# d_main2.net
KiCad netlist of a schematic drawn in EAGLE
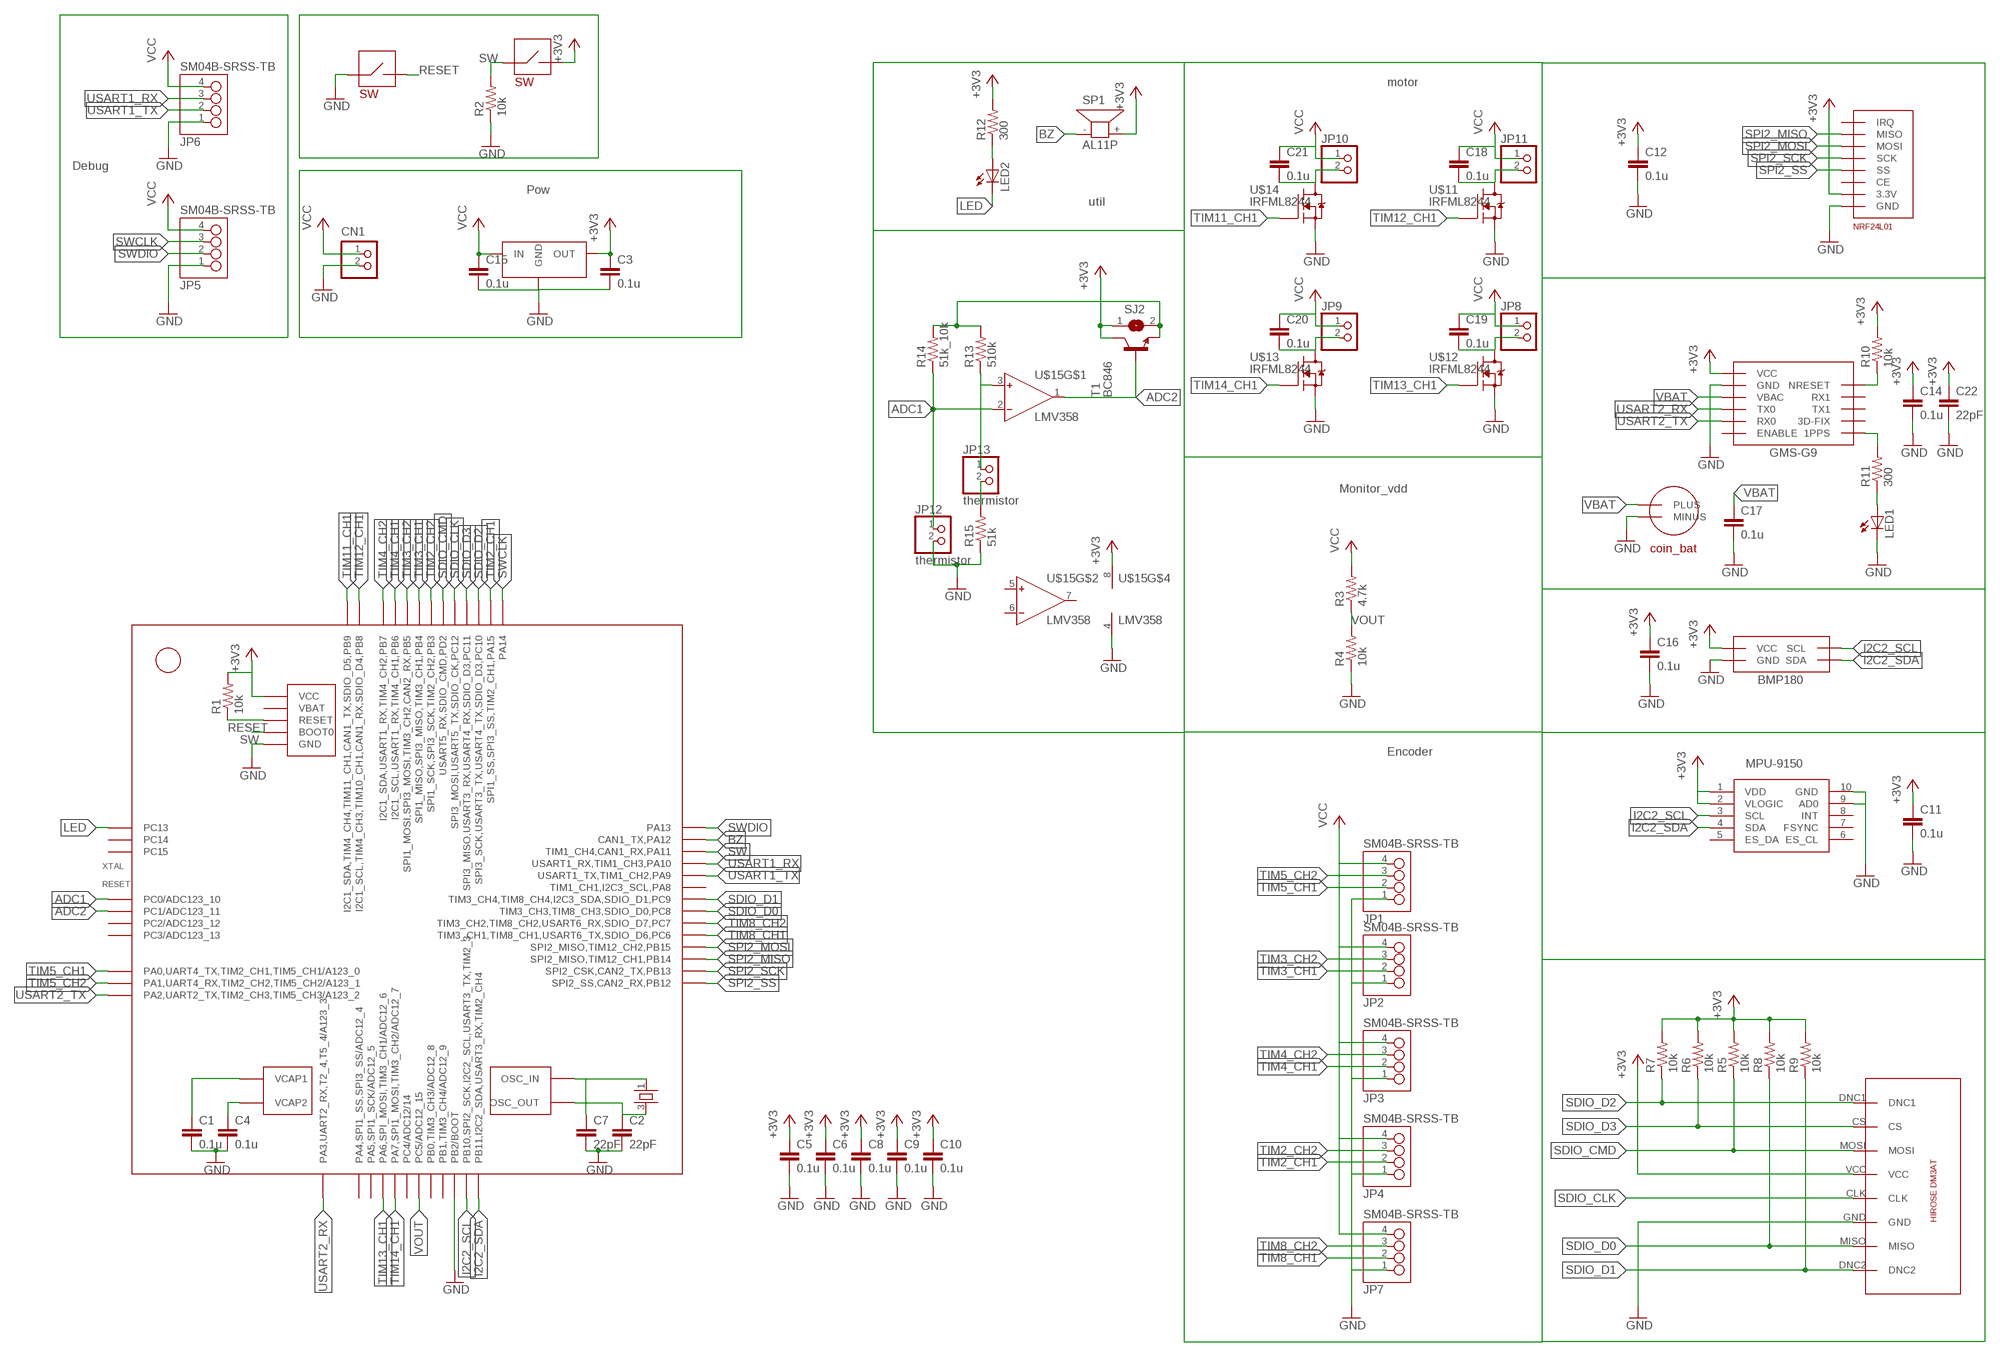
[diagram p0: schematic, sheet 1, part 1 of 2]
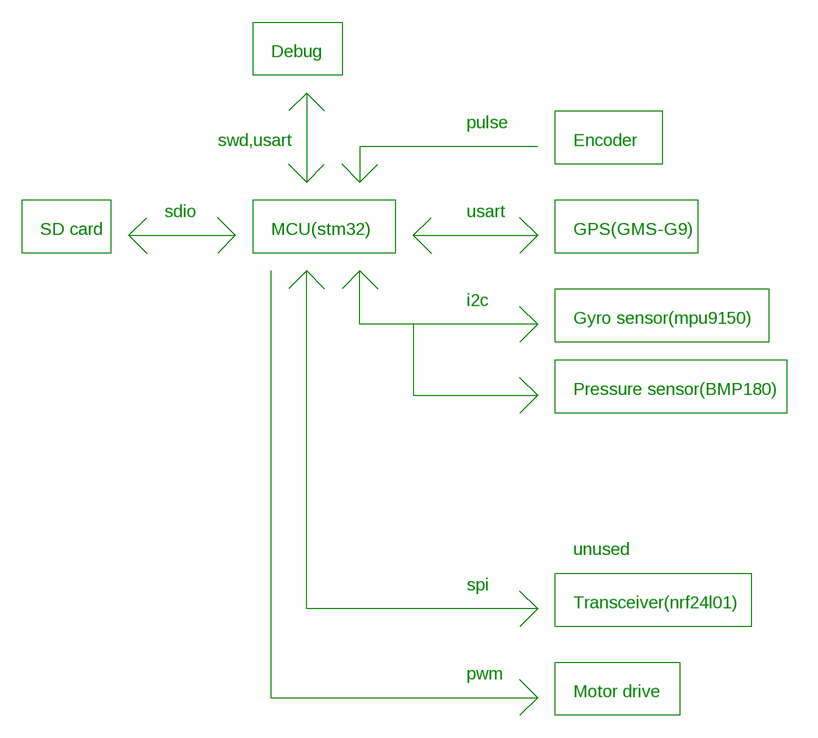
[diagram p1: schematic, sheet 1, part 2 of 2]

(export (version "E")
  (design (tool "Eeschema 10.0.6"))
  (components
    (comp (ref "C1")
      (value "0.1u")
      (footprint "eagle-import:C0603K")
      (libsource (lib "eagle-import") (part "C-EUC0603K"))
    )
    (comp (ref "C2")
      (value "22pF")
      (footprint "eagle-import:C0603K")
      (libsource (lib "eagle-import") (part "C-EUC0603K"))
    )
    (comp (ref "C3")
      (value "0.1u")
      (footprint "eagle-import:C0603K")
      (libsource (lib "eagle-import") (part "C-EUC0603K"))
    )
    (comp (ref "C4")
      (value "0.1u")
      (footprint "eagle-import:C0603K")
      (libsource (lib "eagle-import") (part "C-EUC0603K"))
    )
    (comp (ref "C5")
      (value "0.1u")
      (footprint "eagle-import:C0603K")
      (libsource (lib "eagle-import") (part "C-EUC0603K"))
    )
    (comp (ref "C6")
      (value "0.1u")
      (footprint "eagle-import:C0603K")
      (libsource (lib "eagle-import") (part "C-EUC0603K"))
    )
    (comp (ref "C7")
      (value "22pF")
      (footprint "eagle-import:C0603K")
      (libsource (lib "eagle-import") (part "C-EUC0603K"))
    )
    (comp (ref "C8")
      (value "0.1u")
      (footprint "eagle-import:C0603K")
      (libsource (lib "eagle-import") (part "C-EUC0603K"))
    )
    (comp (ref "C9")
      (value "0.1u")
      (footprint "eagle-import:C0603K")
      (libsource (lib "eagle-import") (part "C-EUC0603K"))
    )
    (comp (ref "C10")
      (value "0.1u")
      (footprint "eagle-import:C0603K")
      (libsource (lib "eagle-import") (part "C-EUC0603K"))
    )
    (comp (ref "C11")
      (value "0.1u")
      (footprint "eagle-import:C0603K")
      (libsource (lib "eagle-import") (part "C-EUC0603K"))
    )
    (comp (ref "C12")
      (value "0.1u")
      (footprint "eagle-import:C0603K")
      (libsource (lib "eagle-import") (part "C-EUC0603K"))
    )
    (comp (ref "C14")
      (value "0.1u")
      (footprint "eagle-import:C0603K")
      (libsource (lib "eagle-import") (part "C-EUC0603K"))
    )
    (comp (ref "C15")
      (value "0.1u")
      (footprint "eagle-import:C0603K")
      (libsource (lib "eagle-import") (part "C-EUC0603K"))
    )
    (comp (ref "C16")
      (value "0.1u")
      (footprint "eagle-import:C0603K")
      (libsource (lib "eagle-import") (part "C-EUC0603K"))
    )
    (comp (ref "C17")
      (value "0.1u")
      (footprint "eagle-import:C0603K")
      (libsource (lib "eagle-import") (part "C-EUC0603K"))
    )
    (comp (ref "C18")
      (value "0.1u")
      (footprint "eagle-import:C0603K")
      (libsource (lib "eagle-import") (part "C-EUC0603K"))
    )
    (comp (ref "C19")
      (value "0.1u")
      (footprint "eagle-import:C0603K")
      (libsource (lib "eagle-import") (part "C-EUC0603K"))
    )
    (comp (ref "C20")
      (value "0.1u")
      (footprint "eagle-import:C0603K")
      (libsource (lib "eagle-import") (part "C-EUC0603K"))
    )
    (comp (ref "C21")
      (value "0.1u")
      (footprint "eagle-import:C0603K")
      (libsource (lib "eagle-import") (part "C-EUC0603K"))
    )
    (comp (ref "C22")
      (value "22pF")
      (footprint "eagle-import:C0603K")
      (libsource (lib "eagle-import") (part "C-EUC0603K"))
    )
    (comp (ref "CN1")
      (value "S2B-XASK-1")
      (footprint "eagle-import:S2B-XASK-1")
      (libsource (lib "eagle-import") (part "S2B-XASK-1"))
    )
    (comp (ref "JP1")
      (value "SM04B-SRSS-TB")
      (footprint "eagle-import:SM04B-SRSS-TB")
      (libsource (lib "eagle-import") (part "SM04B-SRSS-TB"))
    )
    (comp (ref "JP2")
      (value "SM04B-SRSS-TB")
      (footprint "eagle-import:SM04B-SRSS-TB")
      (libsource (lib "eagle-import") (part "SM04B-SRSS-TB"))
    )
    (comp (ref "JP3")
      (value "SM04B-SRSS-TB")
      (footprint "eagle-import:SM04B-SRSS-TB")
      (libsource (lib "eagle-import") (part "SM04B-SRSS-TB"))
    )
    (comp (ref "JP4")
      (value "SM04B-SRSS-TB")
      (footprint "eagle-import:SM04B-SRSS-TB")
      (libsource (lib "eagle-import") (part "SM04B-SRSS-TB"))
    )
    (comp (ref "JP5")
      (value "SM04B-SRSS-TB")
      (footprint "eagle-import:SM04B-SRSS-TB")
      (libsource (lib "eagle-import") (part "SM04B-SRSS-TB"))
    )
    (comp (ref "JP6")
      (value "SM04B-SRSS-TB")
      (footprint "eagle-import:SM04B-SRSS-TB")
      (libsource (lib "eagle-import") (part "SM04B-SRSS-TB"))
    )
    (comp (ref "JP7")
      (value "SM04B-SRSS-TB")
      (footprint "eagle-import:SM04B-SRSS-TB")
      (libsource (lib "eagle-import") (part "SM04B-SRSS-TB"))
    )
    (comp (ref "JP8")
      (value "PINHD-1X2")
      (footprint "eagle-import:1X02")
      (libsource (lib "eagle-import") (part "PINHD-1X2"))
    )
    (comp (ref "JP9")
      (value "PINHD-1X2")
      (footprint "eagle-import:1X02")
      (libsource (lib "eagle-import") (part "PINHD-1X2"))
    )
    (comp (ref "JP10")
      (value "PINHD-1X2")
      (footprint "eagle-import:1X02")
      (libsource (lib "eagle-import") (part "PINHD-1X2"))
    )
    (comp (ref "JP11")
      (value "PINHD-1X2")
      (footprint "eagle-import:1X02")
      (libsource (lib "eagle-import") (part "PINHD-1X2"))
    )
    (comp (ref "JP12")
      (value "thermistor")
      (footprint "eagle-import:1X02")
      (libsource (lib "eagle-import") (part "PINHD-1X2"))
    )
    (comp (ref "JP13")
      (value "thermistor")
      (footprint "eagle-import:1X02")
      (libsource (lib "eagle-import") (part "PINHD-1X2"))
    )
    (comp (ref "LED1")
      (value "LEDCHIP-LED0603")
      (footprint "eagle-import:CHIP-LED0603")
      (libsource (lib "eagle-import") (part "LEDCHIP-LED0603"))
    )
    (comp (ref "LED2")
      (value "LEDCHIP-LED0603")
      (footprint "eagle-import:CHIP-LED0603")
      (libsource (lib "eagle-import") (part "LEDCHIP-LED0603"))
    )
    (comp (ref "R1")
      (value "10k")
      (footprint "eagle-import:R0603")
      (libsource (lib "eagle-import") (part "R-US_R0603"))
    )
    (comp (ref "R2")
      (value "10k")
      (footprint "eagle-import:R0603")
      (libsource (lib "eagle-import") (part "R-US_R0603"))
    )
    (comp (ref "R3")
      (value "4.7k")
      (footprint "eagle-import:R0603")
      (libsource (lib "eagle-import") (part "R-US_R0603"))
    )
    (comp (ref "R4")
      (value "10k")
      (footprint "eagle-import:R0603")
      (libsource (lib "eagle-import") (part "R-US_R0603"))
    )
    (comp (ref "R5")
      (value "10k")
      (footprint "eagle-import:R0603")
      (libsource (lib "eagle-import") (part "R-US_R0603"))
    )
    (comp (ref "R6")
      (value "10k")
      (footprint "eagle-import:R0603")
      (libsource (lib "eagle-import") (part "R-US_R0603"))
    )
    (comp (ref "R7")
      (value "10k")
      (footprint "eagle-import:R0603")
      (libsource (lib "eagle-import") (part "R-US_R0603"))
    )
    (comp (ref "R8")
      (value "10k")
      (footprint "eagle-import:R0603")
      (libsource (lib "eagle-import") (part "R-US_R0603"))
    )
    (comp (ref "R9")
      (value "10k")
      (footprint "eagle-import:R0603")
      (libsource (lib "eagle-import") (part "R-US_R0603"))
    )
    (comp (ref "R10")
      (value "10k")
      (footprint "eagle-import:R0603")
      (libsource (lib "eagle-import") (part "R-US_R0603"))
    )
    (comp (ref "R11")
      (value "300")
      (footprint "eagle-import:R0603")
      (libsource (lib "eagle-import") (part "R-US_R0603"))
    )
    (comp (ref "R12")
      (value "300")
      (footprint "eagle-import:R0603")
      (libsource (lib "eagle-import") (part "R-US_R0603"))
    )
    (comp (ref "R13")
      (value "510k")
      (footprint "eagle-import:R0603")
      (libsource (lib "eagle-import") (part "R-US_R0603"))
    )
    (comp (ref "R14")
      (value "51k_10k")
      (footprint "eagle-import:R0603")
      (libsource (lib "eagle-import") (part "R-US_R0603"))
    )
    (comp (ref "R15")
      (value "51k")
      (footprint "eagle-import:R0603")
      (libsource (lib "eagle-import") (part "R-US_R0603"))
    )
    (comp (ref "SJ2") (value "SJ") (footprint "eagle-import:SJ") (libsource (lib "eagle-import") (part "SJ")))
    (comp (ref "SP1")
      (value "AL11P")
      (footprint "eagle-import:AL11P")
      (libsource (lib "eagle-import") (part "AL11P"))
    )
    (comp (ref "STM32F405RGT6")
      (value "STM32F405_T")
      (footprint "eagle-import:LQFP64")
      (libsource (lib "eagle-import") (part "STM32F405_T"))
    )
    (comp (ref "T1")
      (value "BC846")
      (footprint "eagle-import:SOT23")
      (libsource (lib "eagle-import") (part "BC846"))
    )
    (comp (ref "U$1")
      (value "GMS-G9")
      (footprint "eagle-import:GMS-G9")
      (libsource (lib "eagle-import") (part "GMS-G9"))
    )
    (comp (ref "U$2")
      (value "BMP180")
      (footprint "eagle-import:BMP180")
      (libsource (lib "eagle-import") (part "BMP180"))
    )
    (comp (ref "U$3")
      (value "NRF24L01")
      (footprint "eagle-import:NRF24L01")
      (libsource (lib "eagle-import") (part "NRF24L01"))
    )
    (comp (ref "U$4")
      (value "1056TR")
      (footprint "eagle-import:1056TR")
      (libsource (lib "eagle-import") (part "1056TR"))
    )
    (comp (ref "U$5")
      (value "DM3AT")
      (footprint "eagle-import:DM3AT")
      (libsource (lib "eagle-import") (part "DM3AT"))
    )
    (comp (ref "U$6")
      (value "SWTVBP06-B043CB-B")
      (footprint "eagle-import:SW")
      (libsource (lib "eagle-import") (part "SWTVBP06-B043CB-B"))
    )
    (comp (ref "U$7")
      (value "SWTVBP06-B043CB-B")
      (footprint "eagle-import:SW")
      (libsource (lib "eagle-import") (part "SWTVBP06-B043CB-B"))
    )
    (comp (ref "U$8")
      (value "AP7361-33E")
      (footprint "eagle-import:SOT223")
      (libsource (lib "eagle-import") (part "AP7361-33E"))
    )
    (comp (ref "U$9")
      (value "25MHz")
      (footprint "eagle-import:ASF")
      (libsource (lib "eagle-import") (part "ASF_T"))
    )
    (comp (ref "U$10")
      (value "MPU-9150")
      (footprint "eagle-import:MPU-9150")
      (libsource (lib "eagle-import") (part "MPU-9150"))
    )
    (comp (ref "U$11")
      (value "IRFML8244")
      (footprint "eagle-import:SOT23")
      (libsource (lib "eagle-import") (part "IRFML8244"))
    )
    (comp (ref "U$12")
      (value "IRFML8244")
      (footprint "eagle-import:SOT23")
      (libsource (lib "eagle-import") (part "IRFML8244"))
    )
    (comp (ref "U$13")
      (value "IRFML8244")
      (footprint "eagle-import:SOT23")
      (libsource (lib "eagle-import") (part "IRFML8244"))
    )
    (comp (ref "U$14")
      (value "IRFML8244")
      (footprint "eagle-import:SOT23")
      (libsource (lib "eagle-import") (part "IRFML8244"))
    )
    (comp (ref "U$15")
      (value "LMV358")
      (footprint "eagle-import:SO8")
      (libsource (lib "eagle-import") (part "LMV358"))
    )
  )
  (nets
    (net (code "1") (name "+3V3") (class "Default")
      (node (ref "C10") (pin "1") (pinfunction "1_1") (pintype "passive"))
      (node (ref "C11") (pin "1") (pinfunction "1_1") (pintype "passive"))
      (node (ref "C12") (pin "1") (pinfunction "1_1") (pintype "passive"))
      (node (ref "C14") (pin "1") (pinfunction "1_1") (pintype "passive"))
      (node (ref "C16") (pin "1") (pinfunction "1_1") (pintype "passive"))
      (node (ref "C22") (pin "1") (pinfunction "1_1") (pintype "passive"))
      (node (ref "C3") (pin "1") (pinfunction "1_1") (pintype "passive"))
      (node (ref "C5") (pin "1") (pinfunction "1_1") (pintype "passive"))
      (node (ref "C6") (pin "1") (pinfunction "1_1") (pintype "passive"))
      (node (ref "C8") (pin "1") (pinfunction "1_1") (pintype "passive"))
      (node (ref "C9") (pin "1") (pinfunction "1_1") (pintype "passive"))
      (node (ref "R1") (pin "2") (pinfunction "2_2") (pintype "passive"))
      (node (ref "R10") (pin "2") (pinfunction "2_2") (pintype "passive"))
      (node (ref "R12") (pin "2") (pinfunction "2_2") (pintype "passive"))
      (node (ref "R5") (pin "2") (pinfunction "2_2") (pintype "passive"))
      (node (ref "R6") (pin "2") (pinfunction "2_2") (pintype "passive"))
      (node (ref "R7") (pin "2") (pinfunction "2_2") (pintype "passive"))
      (node (ref "R8") (pin "2") (pinfunction "2_2") (pintype "passive"))
      (node (ref "R9") (pin "2") (pinfunction "2_2") (pintype "passive"))
      (node (ref "SJ2") (pin "1") (pinfunction "1_1") (pintype "passive"))
      (node (ref "SP1") (pin "+") (pinfunction "2_+") (pintype "passive"))
      (node (ref "STM32F405RGT6") (pin "13") (pinfunction "VCC_13") (pintype "bidirectional"))
      (node (ref "STM32F405RGT6") (pin "19") (pinfunction "VCC_19") (pintype "bidirectional"))
      (node (ref "STM32F405RGT6") (pin "32") (pinfunction "VCC_32") (pintype "bidirectional"))
      (node (ref "STM32F405RGT6") (pin "48") (pinfunction "VCC_48") (pintype "bidirectional"))
      (node (ref "STM32F405RGT6") (pin "64") (pinfunction "VCC_64") (pintype "bidirectional"))
      (node (ref "T1") (pin "3") (pinfunction "C_3") (pintype "passive"))
      (node (ref "U$1") (pin "VCC") (pinfunction "VCC_VCC") (pintype "bidirectional"))
      (node (ref "U$10") (pin "1") (pinfunction "VDD_1") (pintype "bidirectional"))
      (node (ref "U$10") (pin "2") (pinfunction "VLOGIC_2") (pintype "bidirectional"))
      (node (ref "U$15") (pin "8") (pinfunction "V+_8") (pintype "power_in"))
      (node (ref "U$2") (pin "VDD") (pinfunction "VCC_VDD") (pintype "bidirectional"))
      (node (ref "U$2") (pin "VDDIO") (pinfunction "VCC_VDDIO") (pintype "bidirectional"))
      (node (ref "U$3") (pin "3.3V") (pinfunction "3.3V_3.3V") (pintype "bidirectional"))
      (node (ref "U$5") (pin "VCC") (pinfunction "VCC_VCC") (pintype "bidirectional"))
      (node (ref "U$7") (pin "P$2") (pinfunction "P$2_P$2") (pintype "bidirectional"))
      (node (ref "U$8") (pin "OUT") (pinfunction "OUT_OUT") (pintype "bidirectional"))
    )
    (net (code "2") (name "/RESET") (class "Default")
      (node (ref "R1") (pin "1") (pinfunction "1_1") (pintype "passive"))
      (node (ref "STM32F405RGT6") (pin "7") (pinfunction "RESET_7") (pintype "bidirectional"))
      (node (ref "U$6") (pin "P$2") (pinfunction "P$2_P$2") (pintype "bidirectional"))
    )
    (net (code "3") (name "ADC1") (class "Default")
      (node (ref "JP12") (pin "1") (pinfunction "1_1") (pintype "passive"))
      (node (ref "R14") (pin "1") (pinfunction "1_1") (pintype "passive"))
      (node (ref "STM32F405RGT6") (pin "8") (pinfunction "PC0/ADC123_10_8") (pintype "bidirectional"))
      (node (ref "U$15") (pin "2") (pinfunction "IN-_2") (pintype "input"))
    )
    (net (code "4") (name "ADC2") (class "Default")
      (node (ref "STM32F405RGT6") (pin "9") (pinfunction "PC1/ADC123_11_9") (pintype "bidirectional"))
      (node (ref "T1") (pin "1") (pinfunction "B_1") (pintype "passive"))
      (node (ref "U$15") (pin "1") (pinfunction "OUT_1") (pintype "output"))
    )
    (net (code "5") (name "BZ") (class "Default")
      (node (ref "SP1") (pin "-") (pinfunction "1_-") (pintype "passive"))
      (node (ref "STM32F405RGT6") (pin "45") (pinfunction "CAN1_TX,PA12_45") (pintype "bidirectional"))
    )
    (net (code "6") (name "GND") (class "Default")
      (node (ref "C1") (pin "2") (pinfunction "2_2") (pintype "passive"))
      (node (ref "C10") (pin "2") (pinfunction "2_2") (pintype "passive"))
      (node (ref "C11") (pin "2") (pinfunction "2_2") (pintype "passive"))
      (node (ref "C12") (pin "2") (pinfunction "2_2") (pintype "passive"))
      (node (ref "C14") (pin "2") (pinfunction "2_2") (pintype "passive"))
      (node (ref "C15") (pin "2") (pinfunction "2_2") (pintype "passive"))
      (node (ref "C16") (pin "2") (pinfunction "2_2") (pintype "passive"))
      (node (ref "C17") (pin "2") (pinfunction "2_2") (pintype "passive"))
      (node (ref "C2") (pin "2") (pinfunction "2_2") (pintype "passive"))
      (node (ref "C22") (pin "2") (pinfunction "2_2") (pintype "passive"))
      (node (ref "C3") (pin "2") (pinfunction "2_2") (pintype "passive"))
      (node (ref "C4") (pin "2") (pinfunction "2_2") (pintype "passive"))
      (node (ref "C5") (pin "2") (pinfunction "2_2") (pintype "passive"))
      (node (ref "C6") (pin "2") (pinfunction "2_2") (pintype "passive"))
      (node (ref "C7") (pin "2") (pinfunction "2_2") (pintype "passive"))
      (node (ref "C8") (pin "2") (pinfunction "2_2") (pintype "passive"))
      (node (ref "C9") (pin "2") (pinfunction "2_2") (pintype "passive"))
      (node (ref "CN1") (pin "2") (pinfunction "2_2") (pintype "passive"))
      (node (ref "JP1") (pin "1") (pinfunction "P$1_1") (pintype "bidirectional"))
      (node (ref "JP12") (pin "2") (pinfunction "2_2") (pintype "passive"))
      (node (ref "JP2") (pin "1") (pinfunction "P$1_1") (pintype "bidirectional"))
      (node (ref "JP3") (pin "1") (pinfunction "P$1_1") (pintype "bidirectional"))
      (node (ref "JP4") (pin "1") (pinfunction "P$1_1") (pintype "bidirectional"))
      (node (ref "JP5") (pin "1") (pinfunction "P$1_1") (pintype "bidirectional"))
      (node (ref "JP6") (pin "1") (pinfunction "P$1_1") (pintype "bidirectional"))
      (node (ref "JP7") (pin "1") (pinfunction "P$1_1") (pintype "bidirectional"))
      (node (ref "LED1") (pin "C") (pinfunction "C_C") (pintype "passive"))
      (node (ref "R15") (pin "1") (pinfunction "1_1") (pintype "passive"))
      (node (ref "R2") (pin "1") (pinfunction "1_1") (pintype "passive"))
      (node (ref "R4") (pin "1") (pinfunction "1_1") (pintype "passive"))
      (node (ref "STM32F405RGT6") (pin "12") (pinfunction "GND_12") (pintype "bidirectional"))
      (node (ref "STM32F405RGT6") (pin "18") (pinfunction "GND_18") (pintype "bidirectional"))
      (node (ref "STM32F405RGT6") (pin "28") (pinfunction "PB2/BOOT_28") (pintype "bidirectional"))
      (node (ref "STM32F405RGT6") (pin "63") (pinfunction "GND_63") (pintype "bidirectional"))
      (node (ref "U$1") (pin "GND") (pinfunction "GND_GND") (pintype "bidirectional"))
      (node (ref "U$1") (pin "GND1") (pinfunction "GND_GND1") (pintype "bidirectional"))
      (node (ref "U$10") (pin "10") (pinfunction "GND_10") (pintype "bidirectional"))
      (node (ref "U$10") (pin "9") (pinfunction "AD0_9") (pintype "bidirectional"))
      (node (ref "U$11") (pin "2") (pinfunction "S_2") (pintype "passive"))
      (node (ref "U$12") (pin "2") (pinfunction "S_2") (pintype "passive"))
      (node (ref "U$13") (pin "2") (pinfunction "S_2") (pintype "passive"))
      (node (ref "U$14") (pin "2") (pinfunction "S_2") (pintype "passive"))
      (node (ref "U$15") (pin "4") (pinfunction "V-_4") (pintype "power_in"))
      (node (ref "U$2") (pin "GND") (pinfunction "GND_GND") (pintype "bidirectional"))
      (node (ref "U$3") (pin "GND") (pinfunction "GND_GND") (pintype "bidirectional"))
      (node (ref "U$4") (pin "MINUS") (pinfunction "MINUS_MINUS") (pintype "bidirectional"))
      (node (ref "U$5") (pin "GND") (pinfunction "GND_GND") (pintype "bidirectional"))
      (node (ref "U$6") (pin "P$1") (pinfunction "P$1_P$1") (pintype "bidirectional"))
      (node (ref "U$8") (pin "GND1") (pinfunction "GND_GND1") (pintype "bidirectional"))
      (node (ref "U$8") (pin "GND2") (pinfunction "GND_GND2") (pintype "bidirectional"))
    )
    (net (code "7") (name "I2C2_SCL") (class "Default")
      (node (ref "STM32F405RGT6") (pin "29") (pinfunction "PB10,SPI2_SCK,I2C2_SCL,USART3_TX,TIM2_3_29") (pintype "bidirectional"))
      (node (ref "U$10") (pin "3") (pinfunction "SCL_3") (pintype "bidirectional"))
      (node (ref "U$2") (pin "SCL") (pinfunction "SCL_SCL") (pintype "bidirectional"))
    )
    (net (code "8") (name "I2C2_SDA") (class "Default")
      (node (ref "STM32F405RGT6") (pin "30") (pinfunction "PB11,I2C2_SDA,USART3_RX,TIM2_CH4_30") (pintype "bidirectional"))
      (node (ref "U$10") (pin "4") (pinfunction "SDA_4") (pintype "bidirectional"))
      (node (ref "U$2") (pin "SDA") (pinfunction "SDA_SDA") (pintype "bidirectional"))
    )
    (net (code "9") (name "LED") (class "Default")
      (node (ref "LED2") (pin "C") (pinfunction "C_C") (pintype "passive"))
      (node (ref "STM32F405RGT6") (pin "2") (pinfunction "PC13_2") (pintype "bidirectional"))
    )
    (net (code "10") (name "Net-(JP13-Pad2)") (class "Default")
      (node (ref "JP13") (pin "2") (pinfunction "2_2") (pintype "passive"))
      (node (ref "R15") (pin "2") (pinfunction "2_2") (pintype "passive"))
    )
    (net (code "11") (name "Net-(LED1-PadA)") (class "Default")
      (node (ref "LED1") (pin "A") (pinfunction "A_A") (pintype "passive"))
      (node (ref "R11") (pin "1") (pinfunction "1_1") (pintype "passive"))
    )
    (net (code "12") (name "Net-(LED2-PadA)") (class "Default")
      (node (ref "LED2") (pin "A") (pinfunction "A_A") (pintype "passive"))
      (node (ref "R12") (pin "1") (pinfunction "1_1") (pintype "passive"))
    )
    (net (code "13") (name "Net-(R10-Pad1)") (class "Default")
      (node (ref "R10") (pin "1") (pinfunction "1_1") (pintype "passive"))
      (node (ref "U$1") (pin "NRESET") (pinfunction "NRESET_NRESET") (pintype "bidirectional"))
    )
    (net (code "14") (name "Net-(R11-Pad2)") (class "Default")
      (node (ref "R11") (pin "2") (pinfunction "2_2") (pintype "passive"))
      (node (ref "U$1") (pin "1PPS") (pinfunction "1PPS_1PPS") (pintype "bidirectional"))
    )
    (net (code "15") (name "Net-(STM32F405RGT6-OSC_IN)") (class "Default")
      (node (ref "C7") (pin "1") (pinfunction "1_1") (pintype "passive"))
      (node (ref "STM32F405RGT6") (pin "5") (pinfunction "OSC_IN_5") (pintype "bidirectional"))
      (node (ref "U$9") (pin "1") (pinfunction "P$1_1") (pintype "bidirectional"))
    )
    (net (code "16") (name "Net-(STM32F405RGT6-OSC_OUT)") (class "Default")
      (node (ref "C2") (pin "1") (pinfunction "1_1") (pintype "passive"))
      (node (ref "STM32F405RGT6") (pin "6") (pinfunction "OSC_OUT_6") (pintype "bidirectional"))
      (node (ref "U$9") (pin "3") (pinfunction "P$2_3") (pintype "bidirectional"))
    )
    (net (code "17") (name "Net-(STM32F405RGT6-VCAP1)") (class "Default")
      (node (ref "C1") (pin "1") (pinfunction "1_1") (pintype "passive"))
      (node (ref "STM32F405RGT6") (pin "31") (pinfunction "VCAP1_31") (pintype "bidirectional"))
    )
    (net (code "18") (name "Net-(STM32F405RGT6-VCAP2)") (class "Default")
      (node (ref "C4") (pin "1") (pinfunction "1_1") (pintype "passive"))
      (node (ref "STM32F405RGT6") (pin "47") (pinfunction "VCAP2_47") (pintype "bidirectional"))
    )
    (net (code "19") (name "Net-(T1-E)") (class "Default")
      (node (ref "R13") (pin "2") (pinfunction "2_2") (pintype "passive"))
      (node (ref "R14") (pin "2") (pinfunction "2_2") (pintype "passive"))
      (node (ref "SJ2") (pin "2") (pinfunction "2_2") (pintype "passive"))
      (node (ref "T1") (pin "2") (pinfunction "E_2") (pintype "passive"))
    )
    (net (code "20") (name "Net-(U$11-D)") (class "Default")
      (node (ref "C18") (pin "2") (pinfunction "2_2") (pintype "passive"))
      (node (ref "JP11") (pin "2") (pinfunction "2_2") (pintype "passive"))
      (node (ref "U$11") (pin "3") (pinfunction "D_3") (pintype "passive"))
    )
    (net (code "21") (name "Net-(U$12-D)") (class "Default")
      (node (ref "C19") (pin "2") (pinfunction "2_2") (pintype "passive"))
      (node (ref "JP8") (pin "2") (pinfunction "2_2") (pintype "passive"))
      (node (ref "U$12") (pin "3") (pinfunction "D_3") (pintype "passive"))
    )
    (net (code "22") (name "Net-(U$13-D)") (class "Default")
      (node (ref "C20") (pin "2") (pinfunction "2_2") (pintype "passive"))
      (node (ref "JP9") (pin "2") (pinfunction "2_2") (pintype "passive"))
      (node (ref "U$13") (pin "3") (pinfunction "D_3") (pintype "passive"))
    )
    (net (code "23") (name "Net-(U$14-D)") (class "Default")
      (node (ref "C21") (pin "2") (pinfunction "2_2") (pintype "passive"))
      (node (ref "JP10") (pin "2") (pinfunction "2_2") (pintype "passive"))
      (node (ref "U$14") (pin "3") (pinfunction "D_3") (pintype "passive"))
    )
    (net (code "24") (name "Net-(U$15A-IN+)") (class "Default")
      (node (ref "JP13") (pin "1") (pinfunction "1_1") (pintype "passive"))
      (node (ref "R13") (pin "1") (pinfunction "1_1") (pintype "passive"))
      (node (ref "U$15") (pin "3") (pinfunction "IN+_3") (pintype "input"))
    )
    (net (code "25") (name "SDIO_CLK") (class "Default")
      (node (ref "STM32F405RGT6") (pin "53") (pinfunction "SPI3_MOSI,USART5_TX,SDIO_CK,PC12_53") (pintype "bidirectional"))
      (node (ref "U$5") (pin "CLK") (pinfunction "CLK_CLK") (pintype "bidirectional"))
    )
    (net (code "26") (name "SDIO_CMD") (class "Default")
      (node (ref "R5") (pin "1") (pinfunction "1_1") (pintype "passive"))
      (node (ref "STM32F405RGT6") (pin "54") (pinfunction "USART5_RX,SDIO_CMD,PD2_54") (pintype "bidirectional"))
      (node (ref "U$5") (pin "MOSI") (pinfunction "MOSI_MOSI") (pintype "bidirectional"))
    )
    (net (code "27") (name "SDIO_D0") (class "Default")
      (node (ref "R8") (pin "1") (pinfunction "1_1") (pintype "passive"))
      (node (ref "STM32F405RGT6") (pin "39") (pinfunction "TIM3_CH3,TIM8_CH3,SDIO_D0,PC8_39") (pintype "bidirectional"))
      (node (ref "U$5") (pin "MISO") (pinfunction "MISO_MISO") (pintype "bidirectional"))
    )
    (net (code "28") (name "SDIO_D1") (class "Default")
      (node (ref "R9") (pin "1") (pinfunction "1_1") (pintype "passive"))
      (node (ref "STM32F405RGT6") (pin "40") (pinfunction "TIM3_CH4,TIM8_CH4,I2C3_SDA,SDIO_D1,PC9_40") (pintype "bidirectional"))
      (node (ref "U$5") (pin "DNC2") (pinfunction "DNC2_DNC2") (pintype "bidirectional"))
    )
    (net (code "29") (name "SDIO_D2") (class "Default")
      (node (ref "R7") (pin "1") (pinfunction "1_1") (pintype "passive"))
      (node (ref "STM32F405RGT6") (pin "51") (pinfunction "SPI3_SCK,USART3_TX,USART4_TX,SDIO_D3,PC10_51") (pintype "bidirectional"))
      (node (ref "U$5") (pin "DNC1") (pinfunction "DNC1_DNC1") (pintype "bidirectional"))
    )
    (net (code "30") (name "SDIO_D3") (class "Default")
      (node (ref "R6") (pin "1") (pinfunction "1_1") (pintype "passive"))
      (node (ref "STM32F405RGT6") (pin "52") (pinfunction "SPI3_MISO,USART3_RX,USART4_RX,SDIO_D3,PC11_52") (pintype "bidirectional"))
      (node (ref "U$5") (pin "CS") (pinfunction "CS_CS") (pintype "bidirectional"))
    )
    (net (code "31") (name "SPI2_MISO") (class "Default")
      (node (ref "STM32F405RGT6") (pin "35") (pinfunction "SPI2_MISO,TIM12_CH1,PB14_35") (pintype "bidirectional"))
      (node (ref "U$3") (pin "MISO") (pinfunction "MISO_MISO") (pintype "bidirectional"))
    )
    (net (code "32") (name "SPI2_MOSI") (class "Default")
      (node (ref "STM32F405RGT6") (pin "36") (pinfunction "SPI2_MISO,TIM12_CH2,PB15_36") (pintype "bidirectional"))
      (node (ref "U$3") (pin "MOSI") (pinfunction "MOSI_MOSI") (pintype "bidirectional"))
    )
    (net (code "33") (name "SPI2_SCK") (class "Default")
      (node (ref "STM32F405RGT6") (pin "34") (pinfunction "SPI2_CSK,CAN2_TX,PB13_34") (pintype "bidirectional"))
      (node (ref "U$3") (pin "SCK") (pinfunction "SCK_SCK") (pintype "bidirectional"))
    )
    (net (code "34") (name "SPI2_SS") (class "Default")
      (node (ref "STM32F405RGT6") (pin "33") (pinfunction "SPI2_SS,CAN2_RX,PB12_33") (pintype "bidirectional"))
      (node (ref "U$3") (pin "SS") (pinfunction "SS_SS") (pintype "bidirectional"))
    )
    (net (code "35") (name "SW") (class "Default")
      (node (ref "R2") (pin "2") (pinfunction "2_2") (pintype "passive"))
      (node (ref "STM32F405RGT6") (pin "44") (pinfunction "TIM1_CH4,CAN1_RX,PA11_44") (pintype "bidirectional"))
      (node (ref "STM32F405RGT6") (pin "60") (pinfunction "BOOT0_60") (pintype "bidirectional"))
      (node (ref "U$7") (pin "P$1") (pinfunction "P$1_P$1") (pintype "bidirectional"))
    )
    (net (code "36") (name "SWCLK") (class "Default")
      (node (ref "JP5") (pin "3") (pinfunction "P$3_3") (pintype "bidirectional"))
      (node (ref "STM32F405RGT6") (pin "49") (pinfunction "PA14_49") (pintype "bidirectional"))
    )
    (net (code "37") (name "SWDIO") (class "Default")
      (node (ref "JP5") (pin "2") (pinfunction "P$2_2") (pintype "bidirectional"))
      (node (ref "STM32F405RGT6") (pin "46") (pinfunction "PA13_46") (pintype "bidirectional"))
    )
    (net (code "38") (name "TIM2_CH1") (class "Default")
      (node (ref "JP4") (pin "2") (pinfunction "P$2_2") (pintype "bidirectional"))
      (node (ref "STM32F405RGT6") (pin "50") (pinfunction "SPI1_SS,SPI3_SS,TIM2_CH1,PA15_50") (pintype "bidirectional"))
    )
    (net (code "39") (name "TIM2_CH2") (class "Default")
      (node (ref "JP4") (pin "3") (pinfunction "P$3_3") (pintype "bidirectional"))
      (node (ref "STM32F405RGT6") (pin "55") (pinfunction "SPI1_SCK,SPI3_SCK,TIM2_CH2,PB3_55") (pintype "bidirectional"))
    )
    (net (code "40") (name "TIM3_CH1") (class "Default")
      (node (ref "JP2") (pin "2") (pinfunction "P$2_2") (pintype "bidirectional"))
      (node (ref "STM32F405RGT6") (pin "56") (pinfunction "SPI1_MISO,SPI3_MISO,TIM3_CH1,PB4_56") (pintype "bidirectional"))
    )
    (net (code "41") (name "TIM3_CH2") (class "Default")
      (node (ref "JP2") (pin "3") (pinfunction "P$3_3") (pintype "bidirectional"))
      (node (ref "STM32F405RGT6") (pin "57") (pinfunction "SPI1_MOSI,SPI3_MOSI,TIM3_CH2,CAN2_RX,PB5_57") (pintype "bidirectional"))
    )
    (net (code "42") (name "TIM4_CH1") (class "Default")
      (node (ref "JP3") (pin "2") (pinfunction "P$2_2") (pintype "bidirectional"))
      (node (ref "STM32F405RGT6") (pin "58") (pinfunction "I2C1_SCL,USART1_RX,TIM4_CH1,PB6_58") (pintype "bidirectional"))
    )
    (net (code "43") (name "TIM4_CH2") (class "Default")
      (node (ref "JP3") (pin "3") (pinfunction "P$3_3") (pintype "bidirectional"))
      (node (ref "STM32F405RGT6") (pin "59") (pinfunction "I2C1_SDA,USART1_RX,TIM4_CH2,PB7_59") (pintype "bidirectional"))
    )
    (net (code "44") (name "TIM5_CH1") (class "Default")
      (node (ref "JP1") (pin "2") (pinfunction "P$2_2") (pintype "bidirectional"))
      (node (ref "STM32F405RGT6") (pin "14") (pinfunction "PA0,UART4_TX,TIM2_CH1,TIM5_CH1/A123_0_14") (pintype "bidirectional"))
    )
    (net (code "45") (name "TIM5_CH2") (class "Default")
      (node (ref "JP1") (pin "3") (pinfunction "P$3_3") (pintype "bidirectional"))
      (node (ref "STM32F405RGT6") (pin "15") (pinfunction "PA1,UART4_RX,TIM2_CH2,TIM5_CH2/A123_1_15") (pintype "bidirectional"))
    )
    (net (code "46") (name "TIM8_CH1") (class "Default")
      (node (ref "JP7") (pin "2") (pinfunction "P$2_2") (pintype "bidirectional"))
      (node (ref "STM32F405RGT6") (pin "37") (pinfunction "TIM3_CH1,TIM8_CH1,USART6_TX,SDIO_D6,PC6_37") (pintype "bidirectional"))
    )
    (net (code "47") (name "TIM8_CH2") (class "Default")
      (node (ref "JP7") (pin "3") (pinfunction "P$3_3") (pintype "bidirectional"))
      (node (ref "STM32F405RGT6") (pin "38") (pinfunction "TIM3_CH2,TIM8_CH2,USART6_RX,SDIO_D7,PC7_38") (pintype "bidirectional"))
    )
    (net (code "48") (name "TIM11_CH1") (class "Default")
      (node (ref "STM32F405RGT6") (pin "62") (pinfunction "I2C1_SDA,TIM4_CH4,TIM11_CH1,CAN1_TX,SDIO_D5,PB9_62") (pintype "bidirectional"))
      (node (ref "U$14") (pin "1") (pinfunction "G_1") (pintype "passive"))
    )
    (net (code "49") (name "TIM12_CH1") (class "Default")
      (node (ref "STM32F405RGT6") (pin "61") (pinfunction "I2C1_SCL,TIM4_CH3,TIM10_CH1,CAN1_RX,SDIO_D4,PB8_61") (pintype "bidirectional"))
      (node (ref "U$11") (pin "1") (pinfunction "G_1") (pintype "passive"))
    )
    (net (code "50") (name "TIM13_CH1") (class "Default")
      (node (ref "STM32F405RGT6") (pin "22") (pinfunction "PA6,SPI_MOSI,TIM3_CH1/ADC12_6_22") (pintype "bidirectional"))
      (node (ref "U$12") (pin "1") (pinfunction "G_1") (pintype "passive"))
    )
    (net (code "51") (name "TIM14_CH1") (class "Default")
      (node (ref "STM32F405RGT6") (pin "23") (pinfunction "PA7,SPI1_MOSI,TIM3_CH2/ADC12_7_23") (pintype "bidirectional"))
      (node (ref "U$13") (pin "1") (pinfunction "G_1") (pintype "passive"))
    )
    (net (code "52") (name "USART1_RX") (class "Default")
      (node (ref "JP6") (pin "3") (pinfunction "P$3_3") (pintype "bidirectional"))
      (node (ref "STM32F405RGT6") (pin "43") (pinfunction "USART1_RX,TIM1_CH3,PA10_43") (pintype "bidirectional"))
    )
    (net (code "53") (name "USART1_TX") (class "Default")
      (node (ref "JP6") (pin "2") (pinfunction "P$2_2") (pintype "bidirectional"))
      (node (ref "STM32F405RGT6") (pin "42") (pinfunction "USART1_TX,TIM1_CH2,PA9_42") (pintype "bidirectional"))
    )
    (net (code "54") (name "USART2_RX") (class "Default")
      (node (ref "STM32F405RGT6") (pin "17") (pinfunction "PA3,UART2_RX,T2_4,T5_4/A123_3_17") (pintype "bidirectional"))
      (node (ref "U$1") (pin "TX0") (pinfunction "TX0_TX0") (pintype "bidirectional"))
    )
    (net (code "55") (name "USART2_TX") (class "Default")
      (node (ref "STM32F405RGT6") (pin "16") (pinfunction "PA2,UART2_TX,TIM2_CH3,TIM5_CH3/A123_2_16") (pintype "bidirectional"))
      (node (ref "U$1") (pin "RX0") (pinfunction "RX0_RX0") (pintype "bidirectional"))
    )
    (net (code "56") (name "VBAT") (class "Default")
      (node (ref "C17") (pin "1") (pinfunction "1_1") (pintype "passive"))
      (node (ref "U$1") (pin "VBAC") (pinfunction "VBAC_VBAC") (pintype "bidirectional"))
      (node (ref "U$4") (pin "PLUS") (pinfunction "PLUS_PLUS") (pintype "bidirectional"))
    )
    (net (code "57") (name "VCC") (class "Default")
      (node (ref "C15") (pin "1") (pinfunction "1_1") (pintype "passive"))
      (node (ref "C18") (pin "1") (pinfunction "1_1") (pintype "passive"))
      (node (ref "C19") (pin "1") (pinfunction "1_1") (pintype "passive"))
      (node (ref "C20") (pin "1") (pinfunction "1_1") (pintype "passive"))
      (node (ref "C21") (pin "1") (pinfunction "1_1") (pintype "passive"))
      (node (ref "CN1") (pin "1") (pinfunction "1_1") (pintype "passive"))
      (node (ref "JP1") (pin "4") (pinfunction "P$4_4") (pintype "bidirectional"))
      (node (ref "JP10") (pin "1") (pinfunction "1_1") (pintype "passive"))
      (node (ref "JP11") (pin "1") (pinfunction "1_1") (pintype "passive"))
      (node (ref "JP2") (pin "4") (pinfunction "P$4_4") (pintype "bidirectional"))
      (node (ref "JP3") (pin "4") (pinfunction "P$4_4") (pintype "bidirectional"))
      (node (ref "JP4") (pin "4") (pinfunction "P$4_4") (pintype "bidirectional"))
      (node (ref "JP5") (pin "4") (pinfunction "P$4_4") (pintype "bidirectional"))
      (node (ref "JP6") (pin "4") (pinfunction "P$4_4") (pintype "bidirectional"))
      (node (ref "JP7") (pin "4") (pinfunction "P$4_4") (pintype "bidirectional"))
      (node (ref "JP8") (pin "1") (pinfunction "1_1") (pintype "passive"))
      (node (ref "JP9") (pin "1") (pinfunction "1_1") (pintype "passive"))
      (node (ref "R3") (pin "2") (pinfunction "2_2") (pintype "passive"))
      (node (ref "U$8") (pin "IN") (pinfunction "IN_IN") (pintype "bidirectional"))
    )
    (net (code "58") (name "VOUT") (class "Default")
      (node (ref "R3") (pin "1") (pinfunction "1_1") (pintype "passive"))
      (node (ref "R4") (pin "2") (pinfunction "2_2") (pintype "passive"))
      (node (ref "STM32F405RGT6") (pin "25") (pinfunction "PC5/ADC12_15_25") (pintype "bidirectional"))
    )
    (net (code "59") (name "unconnected-(STM32F405RGT6-PA4,SPI1_SS,SPI3_SS{slash}ADC12_4-Pad20)") (class "Default")
      (node (ref "STM32F405RGT6") (pin "20") (pinfunction "PA4,SPI1_SS,SPI3_SS/ADC12_4_20") (pintype "bidirectional"))
    )
    (net (code "60") (name "unconnected-(STM32F405RGT6-PA5,SPI1_SCK{slash}ADC12_5-Pad21)") (class "Default")
      (node (ref "STM32F405RGT6") (pin "21") (pinfunction "PA5,SPI1_SCK/ADC12_5_21") (pintype "bidirectional"))
    )
    (net (code "61") (name "unconnected-(STM32F405RGT6-PB0,TIM3_CH3{slash}ADC12_8-Pad26)") (class "Default")
      (node (ref "STM32F405RGT6") (pin "26") (pinfunction "PB0,TIM3_CH3/ADC12_8_26") (pintype "bidirectional"))
    )
    (net (code "62") (name "unconnected-(STM32F405RGT6-PB1,TIM3_CH4{slash}ADC12_9-Pad27)") (class "Default")
      (node (ref "STM32F405RGT6") (pin "27") (pinfunction "PB1,TIM3_CH4/ADC12_9_27") (pintype "bidirectional"))
    )
    (net (code "63") (name "unconnected-(STM32F405RGT6-PC2{slash}ADC123_12-Pad10)") (class "Default")
      (node (ref "STM32F405RGT6") (pin "10") (pinfunction "PC2/ADC123_12_10") (pintype "bidirectional"))
    )
    (net (code "64") (name "unconnected-(STM32F405RGT6-PC3{slash}ADC123_13-Pad11)") (class "Default")
      (node (ref "STM32F405RGT6") (pin "11") (pinfunction "PC3/ADC123_13_11") (pintype "bidirectional"))
    )
    (net (code "65") (name "unconnected-(STM32F405RGT6-PC4{slash}ADC12{slash}14-Pad24)") (class "Default")
      (node (ref "STM32F405RGT6") (pin "24") (pinfunction "PC4/ADC12/14_24") (pintype "bidirectional"))
    )
    (net (code "66") (name "unconnected-(STM32F405RGT6-PC14-Pad3)") (class "Default")
      (node (ref "STM32F405RGT6") (pin "3") (pinfunction "PC14_3") (pintype "bidirectional"))
    )
    (net (code "67") (name "unconnected-(STM32F405RGT6-PC15-Pad4)") (class "Default")
      (node (ref "STM32F405RGT6") (pin "4") (pinfunction "PC15_4") (pintype "bidirectional"))
    )
    (net (code "68") (name "unconnected-(STM32F405RGT6-TIM1_CH1,I2C3_SCL,PA8-Pad41)") (class "Default")
      (node (ref "STM32F405RGT6") (pin "41") (pinfunction "TIM1_CH1,I2C3_SCL,PA8_41") (pintype "bidirectional"))
    )
    (net (code "69") (name "unconnected-(STM32F405RGT6-VBAT-Pad1)") (class "Default")
      (node (ref "STM32F405RGT6") (pin "1") (pinfunction "VBAT_1") (pintype "bidirectional"))
    )
    (net (code "70") (name "unconnected-(U$1-Pad3D-FIX)") (class "Default")
      (node (ref "U$1") (pin "3D-FIX") (pinfunction "3D-FIX_3D-FIX") (pintype "bidirectional"))
    )
    (net (code "71") (name "unconnected-(U$1-PadENABLE)") (class "Default")
      (node (ref "U$1") (pin "ENABLE") (pinfunction "ENABLE_ENABLE") (pintype "bidirectional"))
    )
    (net (code "72") (name "unconnected-(U$1-PadRX1)") (class "Default")
      (node (ref "U$1") (pin "RX1") (pinfunction "RX1_RX1") (pintype "bidirectional"))
    )
    (net (code "73") (name "unconnected-(U$1-PadTX1)") (class "Default")
      (node (ref "U$1") (pin "TX1") (pinfunction "TX1_TX1") (pintype "bidirectional"))
    )
    (net (code "74") (name "unconnected-(U$3-PadCE)") (class "Default")
      (node (ref "U$3") (pin "CE") (pinfunction "CE_CE") (pintype "bidirectional"))
    )
    (net (code "75") (name "unconnected-(U$3-PadIRQ)") (class "Default")
      (node (ref "U$3") (pin "IRQ") (pinfunction "IRQ_IRQ") (pintype "bidirectional"))
    )
    (net (code "76") (name "unconnected-(U$10-ES_CL-Pad6)") (class "Default")
      (node (ref "U$10") (pin "6") (pinfunction "ES_CL_6") (pintype "bidirectional"))
    )
    (net (code "77") (name "unconnected-(U$10-ES_DA-Pad5)") (class "Default")
      (node (ref "U$10") (pin "5") (pinfunction "ES_DA_5") (pintype "bidirectional"))
    )
    (net (code "78") (name "unconnected-(U$10-FSYNC-Pad7)") (class "Default")
      (node (ref "U$10") (pin "7") (pinfunction "FSYNC_7") (pintype "bidirectional"))
    )
    (net (code "79") (name "unconnected-(U$10-INT-Pad8)") (class "Default")
      (node (ref "U$10") (pin "8") (pinfunction "INT_8") (pintype "bidirectional"))
    )
    (net (code "80") (name "unconnected-(U$15B-IN+-Pad5)") (class "Default")
      (node (ref "U$15") (pin "5") (pinfunction "IN+_5") (pintype "input"))
    )
    (net (code "81") (name "unconnected-(U$15B-IN--Pad6)") (class "Default")
      (node (ref "U$15") (pin "6") (pinfunction "IN-_6") (pintype "input"))
    )
    (net (code "82") (name "unconnected-(U$15B-OUT-Pad7)") (class "Default")
      (node (ref "U$15") (pin "7") (pinfunction "OUT_7") (pintype "output"))
    )
  )
)
